# Full-tDCS-1.net
KiCad netlist of a schematic drawn in EAGLE
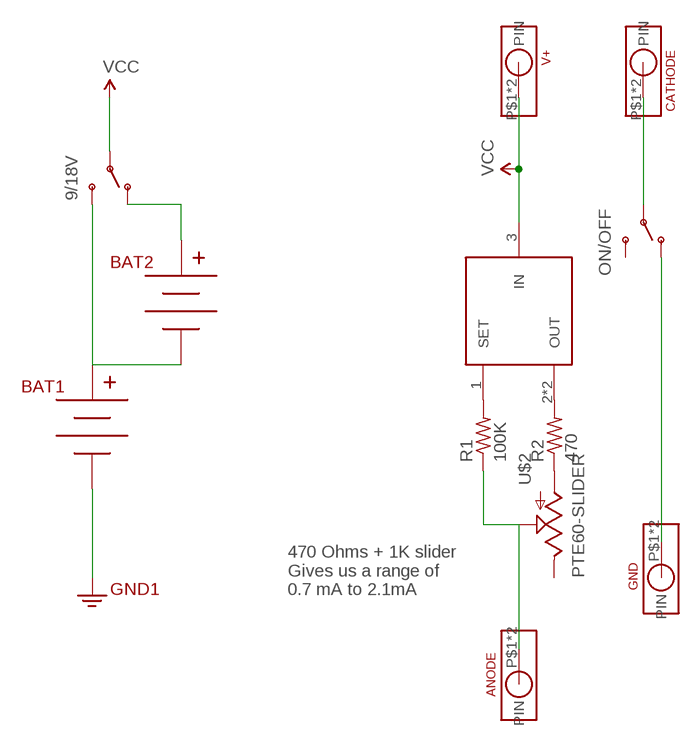
[diagram p0: schematic, sheet 1]

(export (version "E")
  (design (tool "Eeschema 10.0.6"))
  (components
    (comp (ref "9/18V")
      (value "SWITCH-SPDTPTH")
      (footprint "eagle-import:SWITCH-SPDT")
      (libsource (lib "eagle-import") (part "SWITCH-SPDTPTH"))
    )
    (comp (ref "ANODE")
      (value "BANANA-JACK")
      (footprint "eagle-import:105-0753-001-BANANA-JACK")
      (libsource (lib "eagle-import") (part "BANANA-JACK"))
    )
    (comp (ref "BAT1")
      (value "BC9VPC")
      (footprint "eagle-import:BC9VPC")
      (libsource (lib "eagle-import") (part "BC9VPC"))
    )
    (comp (ref "BAT2")
      (value "BC9VPC")
      (footprint "eagle-import:BC9VPC")
      (libsource (lib "eagle-import") (part "BC9VPC"))
    )
    (comp (ref "CATHODE")
      (value "BANANA-JACK")
      (footprint "eagle-import:105-0753-001-BANANA-JACK")
      (libsource (lib "eagle-import") (part "BANANA-JACK"))
    )
    (comp (ref "GND")
      (value "BANANA-JACK")
      (footprint "eagle-import:105-0753-001-BANANA-JACK")
      (libsource (lib "eagle-import") (part "BANANA-JACK"))
    )
    (comp (ref "ON/OFF")
      (value "SWITCH-SPDTPTH")
      (footprint "eagle-import:SWITCH-SPDT")
      (libsource (lib "eagle-import") (part "SWITCH-SPDTPTH"))
    )
    (comp (ref "R1")
      (value "100K")
      (footprint "eagle-import:0204_7")
      (libsource (lib "eagle-import") (part "R-US_0204/7"))
    )
    (comp (ref "R2")
      (value "470")
      (footprint "eagle-import:0204_7")
      (libsource (lib "eagle-import") (part "R-US_0204/7"))
    )
    (comp (ref "U$1")
      (value "LT3092")
      (footprint "eagle-import:SOT223")
      (libsource (lib "eagle-import") (part "LT3092-SOT-223"))
    )
    (comp (ref "U$2")
      (value "PTE60-SLIDER")
      (footprint "eagle-import:SLIDER")
      (libsource (lib "eagle-import") (part "PTE60-SLIDER"))
    )
    (comp (ref "V+")
      (value "BANANA-JACK")
      (footprint "eagle-import:105-0753-001-BANANA-JACK")
      (libsource (lib "eagle-import") (part "BANANA-JACK"))
    )
  )
  (nets
    (net (code "1") (name "GND2") (class "Default")
      (node (ref "BAT1") (pin "V-") (pinfunction "V-_V-") (pintype "bidirectional"))
      (node (ref "GND") (pin "P$1") (pinfunction "PIN_P$1") (pintype "bidirectional"))
      (node (ref "GND") (pin "P$2") (pinfunction "PIN_P$2") (pintype "bidirectional"))
      (node (ref "ON/OFF") (pin "1") (pinfunction "O_1") (pintype "passive"))
    )
    (net (code "2") (name "Net-(9/18V-O)") (class "Default")
      (node (ref "9/18V") (pin "1") (pinfunction "O_1") (pintype "passive"))
      (node (ref "BAT2") (pin "V+") (pinfunction "V+_V+") (pintype "bidirectional"))
    )
    (net (code "3") (name "Net-(9/18V-S)") (class "Default")
      (node (ref "9/18V") (pin "3") (pinfunction "S_3") (pintype "passive"))
      (node (ref "BAT1") (pin "V+") (pinfunction "V+_V+") (pintype "bidirectional"))
      (node (ref "BAT2") (pin "V-") (pinfunction "V-_V-") (pintype "bidirectional"))
    )
    (net (code "4") (name "Net-(ON/OFF-P)") (class "Default")
      (node (ref "CATHODE") (pin "P$1") (pinfunction "PIN_P$1") (pintype "bidirectional"))
      (node (ref "CATHODE") (pin "P$2") (pinfunction "PIN_P$2") (pintype "bidirectional"))
      (node (ref "ON/OFF") (pin "2") (pinfunction "P_2") (pintype "passive"))
    )
    (net (code "5") (name "Net-(R2-Pad2)") (class "Default")
      (node (ref "R2") (pin "2") (pinfunction "2_2") (pintype "passive"))
      (node (ref "U$1") (pin "2") (pinfunction "OUT_2") (pintype "bidirectional"))
      (node (ref "U$1") (pin "4") (pinfunction "OUT_4") (pintype "bidirectional"))
    )
    (net (code "6") (name "Net-(U$1-SET)") (class "Default")
      (node (ref "R1") (pin "2") (pinfunction "2_2") (pintype "passive"))
      (node (ref "U$1") (pin "1") (pinfunction "SET_1") (pintype "bidirectional"))
    )
    (net (code "7") (name "Net-(U$2-A)") (class "Default")
      (node (ref "R2") (pin "1") (pinfunction "1_1") (pintype "passive"))
      (node (ref "U$2") (pin "1") (pinfunction "A_1") (pintype "passive"))
    )
    (net (code "8") (name "Net-(U$2-S)") (class "Default")
      (node (ref "ANODE") (pin "P$1") (pinfunction "PIN_P$1") (pintype "bidirectional"))
      (node (ref "ANODE") (pin "P$2") (pinfunction "PIN_P$2") (pintype "bidirectional"))
      (node (ref "R1") (pin "1") (pinfunction "1_1") (pintype "passive"))
      (node (ref "U$2") (pin "2") (pinfunction "S_2") (pintype "passive"))
    )
    (net (code "9") (name "VCC") (class "Default")
      (node (ref "9/18V") (pin "2") (pinfunction "P_2") (pintype "passive"))
      (node (ref "U$1") (pin "3") (pinfunction "IN_3") (pintype "bidirectional"))
      (node (ref "V+") (pin "P$1") (pinfunction "PIN_P$1") (pintype "bidirectional"))
      (node (ref "V+") (pin "P$2") (pinfunction "PIN_P$2") (pintype "bidirectional"))
    )
    (net (code "10") (name "unconnected-(ON/OFF-S-Pad3)") (class "Default")
      (node (ref "ON/OFF") (pin "3") (pinfunction "S_3") (pintype "passive"))
    )
    (net (code "11") (name "unconnected-(U$2-E-Pad3)") (class "Default")
      (node (ref "U$2") (pin "3") (pinfunction "E_3") (pintype "passive"))
    )
  )
)
